# Drive.net
KiCad netlist of a schematic drawn in Altium Designer
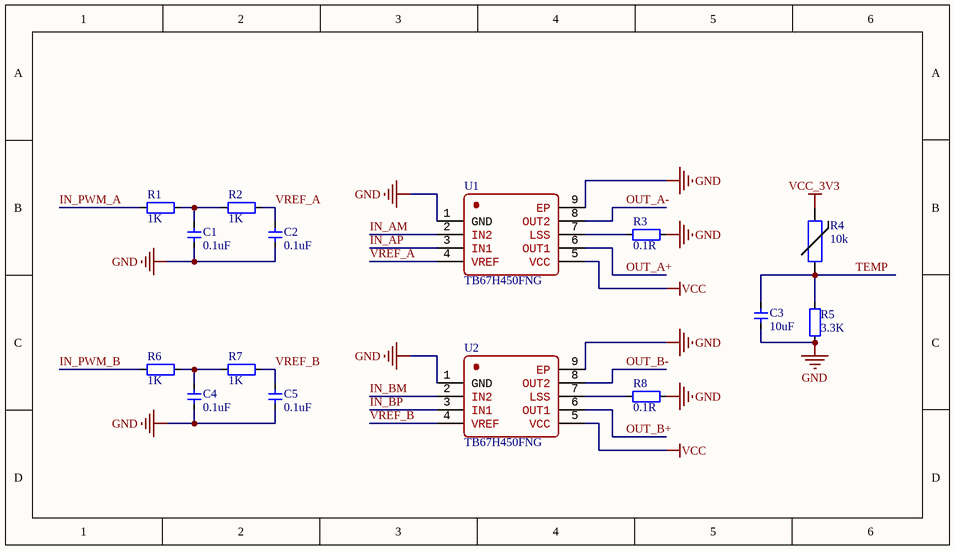
[diagram p0: Drive.SchDoc]

(export (version "E")
  (design (tool "Eeschema 10.0.6"))
  (components
    (comp (ref "C1")
      (value "0.1uF")
      (footprint "CAP_0402")
      (description "Capacitor")
      (libsource (lib "MyPcbLib") (part "电容-0402"))
    )
    (comp (ref "C2")
      (value "0.1uF")
      (footprint "CAP_0402")
      (description "Capacitor")
      (libsource (lib "MyPcbLib") (part "电容-0402"))
    )
    (comp (ref "C3")
      (value "10uF")
      (footprint "CAP_0402")
      (description "Capacitor")
      (libsource (lib "MyPcbLib") (part "电容-0402"))
    )
    (comp (ref "C4")
      (value "0.1uF")
      (footprint "CAP_0402")
      (description "Capacitor")
      (libsource (lib "MyPcbLib") (part "电容-0402"))
    )
    (comp (ref "C5")
      (value "0.1uF")
      (footprint "CAP_0402")
      (description "Capacitor")
      (libsource (lib "MyPcbLib") (part "电容-0402"))
    )
    (comp (ref "R1")
      (value "1K")
      (footprint "RES_0402")
      (description "Resistor")
      (libsource (lib "") (part "电阻-0402_1"))
    )
    (comp (ref "R2")
      (value "1K")
      (footprint "RES_0402")
      (description "Resistor")
      (libsource (lib "") (part "电阻-0402_1"))
    )
    (comp (ref "R3")
      (value "0.1R")
      (footprint "1206-RES")
      (description "Resistor")
      (libsource (lib "MyPcbLib") (part "电阻-1206"))
    )
    (comp (ref "R4")
      (value "10k")
      (footprint "RES_0402")
      (description "THERMISTOR 10K OHM NTC 0402 SMD")
      (fields (field (name "Comment") "NCP15XH103F03RC"))
      (libsource (lib "MyPcbLib") (part "NCP15XH103F03RC"))
    )
    (comp (ref "R5")
      (value "3.3K")
      (footprint "RES_0402")
      (description "Resistor")
      (libsource (lib "MyPcbLib") (part "电阻-0402"))
    )
    (comp (ref "R6")
      (value "1K")
      (footprint "RES_0402")
      (description "Resistor")
      (libsource (lib "") (part "电阻-0402_1"))
    )
    (comp (ref "R7")
      (value "1K")
      (footprint "RES_0402")
      (description "Resistor")
      (libsource (lib "") (part "电阻-0402_1"))
    )
    (comp (ref "R8")
      (value "0.1R")
      (footprint "1206-RES")
      (description "Resistor")
      (libsource (lib "MyPcbLib") (part "电阻-1206"))
    )
    (comp (ref "U1")
      (value "TB67H450FNG")
      (footprint "SO-8-PAD")
      (description "PWM Chopper Type DC Brushed Motor Driver")
      (libsource (lib "MyPcbLib") (part "TB67H450FNG"))
    )
    (comp (ref "U2")
      (value "TB67H450FNG")
      (footprint "SO-8-PAD")
      (description "PWM Chopper Type DC Brushed Motor Driver")
      (libsource (lib "MyPcbLib") (part "TB67H450FNG"))
    )
  )
  (nets
    (net (code "1") (name "/IN_AM") (class "Default")
      (node (ref "U1") (pin "2") (pinfunction "IN2_2") (pintype "passive"))
    )
    (net (code "2") (name "/IN_AP") (class "Default")
      (node (ref "U1") (pin "3") (pinfunction "IN1_3") (pintype "passive"))
    )
    (net (code "3") (name "/IN_BM") (class "Default")
      (node (ref "U2") (pin "2") (pinfunction "IN2_2") (pintype "passive"))
    )
    (net (code "4") (name "/IN_BP") (class "Default")
      (node (ref "U2") (pin "3") (pinfunction "IN1_3") (pintype "passive"))
    )
    (net (code "5") (name "/IN_PWM_A") (class "Default")
      (node (ref "R1") (pin "1") (pinfunction "1_1") (pintype "passive"))
    )
    (net (code "6") (name "/IN_PWM_B") (class "Default")
      (node (ref "R6") (pin "1") (pinfunction "1_1") (pintype "passive"))
    )
    (net (code "7") (name "/OUT_A+") (class "Default")
      (node (ref "U1") (pin "6") (pinfunction "OUT1_6") (pintype "passive"))
    )
    (net (code "8") (name "/OUT_A-") (class "Default")
      (node (ref "U1") (pin "8") (pinfunction "OUT2_8") (pintype "passive"))
    )
    (net (code "9") (name "/OUT_B+") (class "Default")
      (node (ref "U2") (pin "6") (pinfunction "OUT1_6") (pintype "passive"))
    )
    (net (code "10") (name "/OUT_B-") (class "Default")
      (node (ref "U2") (pin "8") (pinfunction "OUT2_8") (pintype "passive"))
    )
    (net (code "11") (name "/TEMP") (class "Default")
      (node (ref "C3") (pin "2") (pinfunction "2_2") (pintype "passive"))
      (node (ref "R4") (pin "1") (pinfunction "0_1") (pintype "passive"))
      (node (ref "R5") (pin "2") (pinfunction "2_2") (pintype "passive"))
    )
    (net (code "12") (name "/VREF_A") (class "Default")
      (node (ref "C2") (pin "2") (pinfunction "2_2") (pintype "passive"))
      (node (ref "R2") (pin "2") (pinfunction "2_2") (pintype "passive"))
      (node (ref "U1") (pin "4") (pinfunction "VREF_4") (pintype "passive"))
    )
    (net (code "13") (name "/VREF_B") (class "Default")
      (node (ref "C5") (pin "2") (pinfunction "2_2") (pintype "passive"))
      (node (ref "R7") (pin "2") (pinfunction "2_2") (pintype "passive"))
      (node (ref "U2") (pin "4") (pinfunction "VREF_4") (pintype "passive"))
    )
    (net (code "14") (name "GND") (class "Default")
      (node (ref "C1") (pin "1") (pinfunction "1_1") (pintype "passive"))
      (node (ref "C2") (pin "1") (pinfunction "1_1") (pintype "passive"))
      (node (ref "C3") (pin "1") (pinfunction "1_1") (pintype "passive"))
      (node (ref "C4") (pin "1") (pinfunction "1_1") (pintype "passive"))
      (node (ref "C5") (pin "1") (pinfunction "1_1") (pintype "passive"))
      (node (ref "R3") (pin "2") (pinfunction "2_2") (pintype "passive"))
      (node (ref "R5") (pin "1") (pinfunction "1_1") (pintype "passive"))
      (node (ref "R8") (pin "2") (pinfunction "2_2") (pintype "passive"))
      (node (ref "U1") (pin "1") (pinfunction "GND_1") (pintype "passive"))
      (node (ref "U1") (pin "9") (pinfunction "EP_9") (pintype "passive"))
      (node (ref "U2") (pin "1") (pinfunction "GND_1") (pintype "passive"))
      (node (ref "U2") (pin "9") (pinfunction "EP_9") (pintype "passive"))
    )
    (net (code "15") (name "Net-(C1-Pad2)") (class "Default")
      (node (ref "C1") (pin "2") (pinfunction "2_2") (pintype "passive"))
      (node (ref "R1") (pin "2") (pinfunction "2_2") (pintype "passive"))
      (node (ref "R2") (pin "1") (pinfunction "1_1") (pintype "passive"))
    )
    (net (code "16") (name "Net-(C4-Pad2)") (class "Default")
      (node (ref "C4") (pin "2") (pinfunction "2_2") (pintype "passive"))
      (node (ref "R6") (pin "2") (pinfunction "2_2") (pintype "passive"))
      (node (ref "R7") (pin "1") (pinfunction "1_1") (pintype "passive"))
    )
    (net (code "17") (name "Net-(U1-LSS)") (class "Default")
      (node (ref "R3") (pin "1") (pinfunction "1_1") (pintype "passive"))
      (node (ref "U1") (pin "7") (pinfunction "LSS_7") (pintype "passive"))
    )
    (net (code "18") (name "Net-(U2-LSS)") (class "Default")
      (node (ref "R8") (pin "1") (pinfunction "1_1") (pintype "passive"))
      (node (ref "U2") (pin "7") (pinfunction "LSS_7") (pintype "passive"))
    )
    (net (code "19") (name "VCC") (class "Default")
      (node (ref "U1") (pin "5") (pinfunction "VCC_5") (pintype "passive"))
      (node (ref "U2") (pin "5") (pinfunction "VCC_5") (pintype "passive"))
    )
    (net (code "20") (name "VCC_3V3") (class "Default")
      (node (ref "R4") (pin "2") (pinfunction "0_2") (pintype "passive"))
    )
  )
)
